# STM32F407_2.net
KiCad netlist of a schematic drawn in Altium Designer
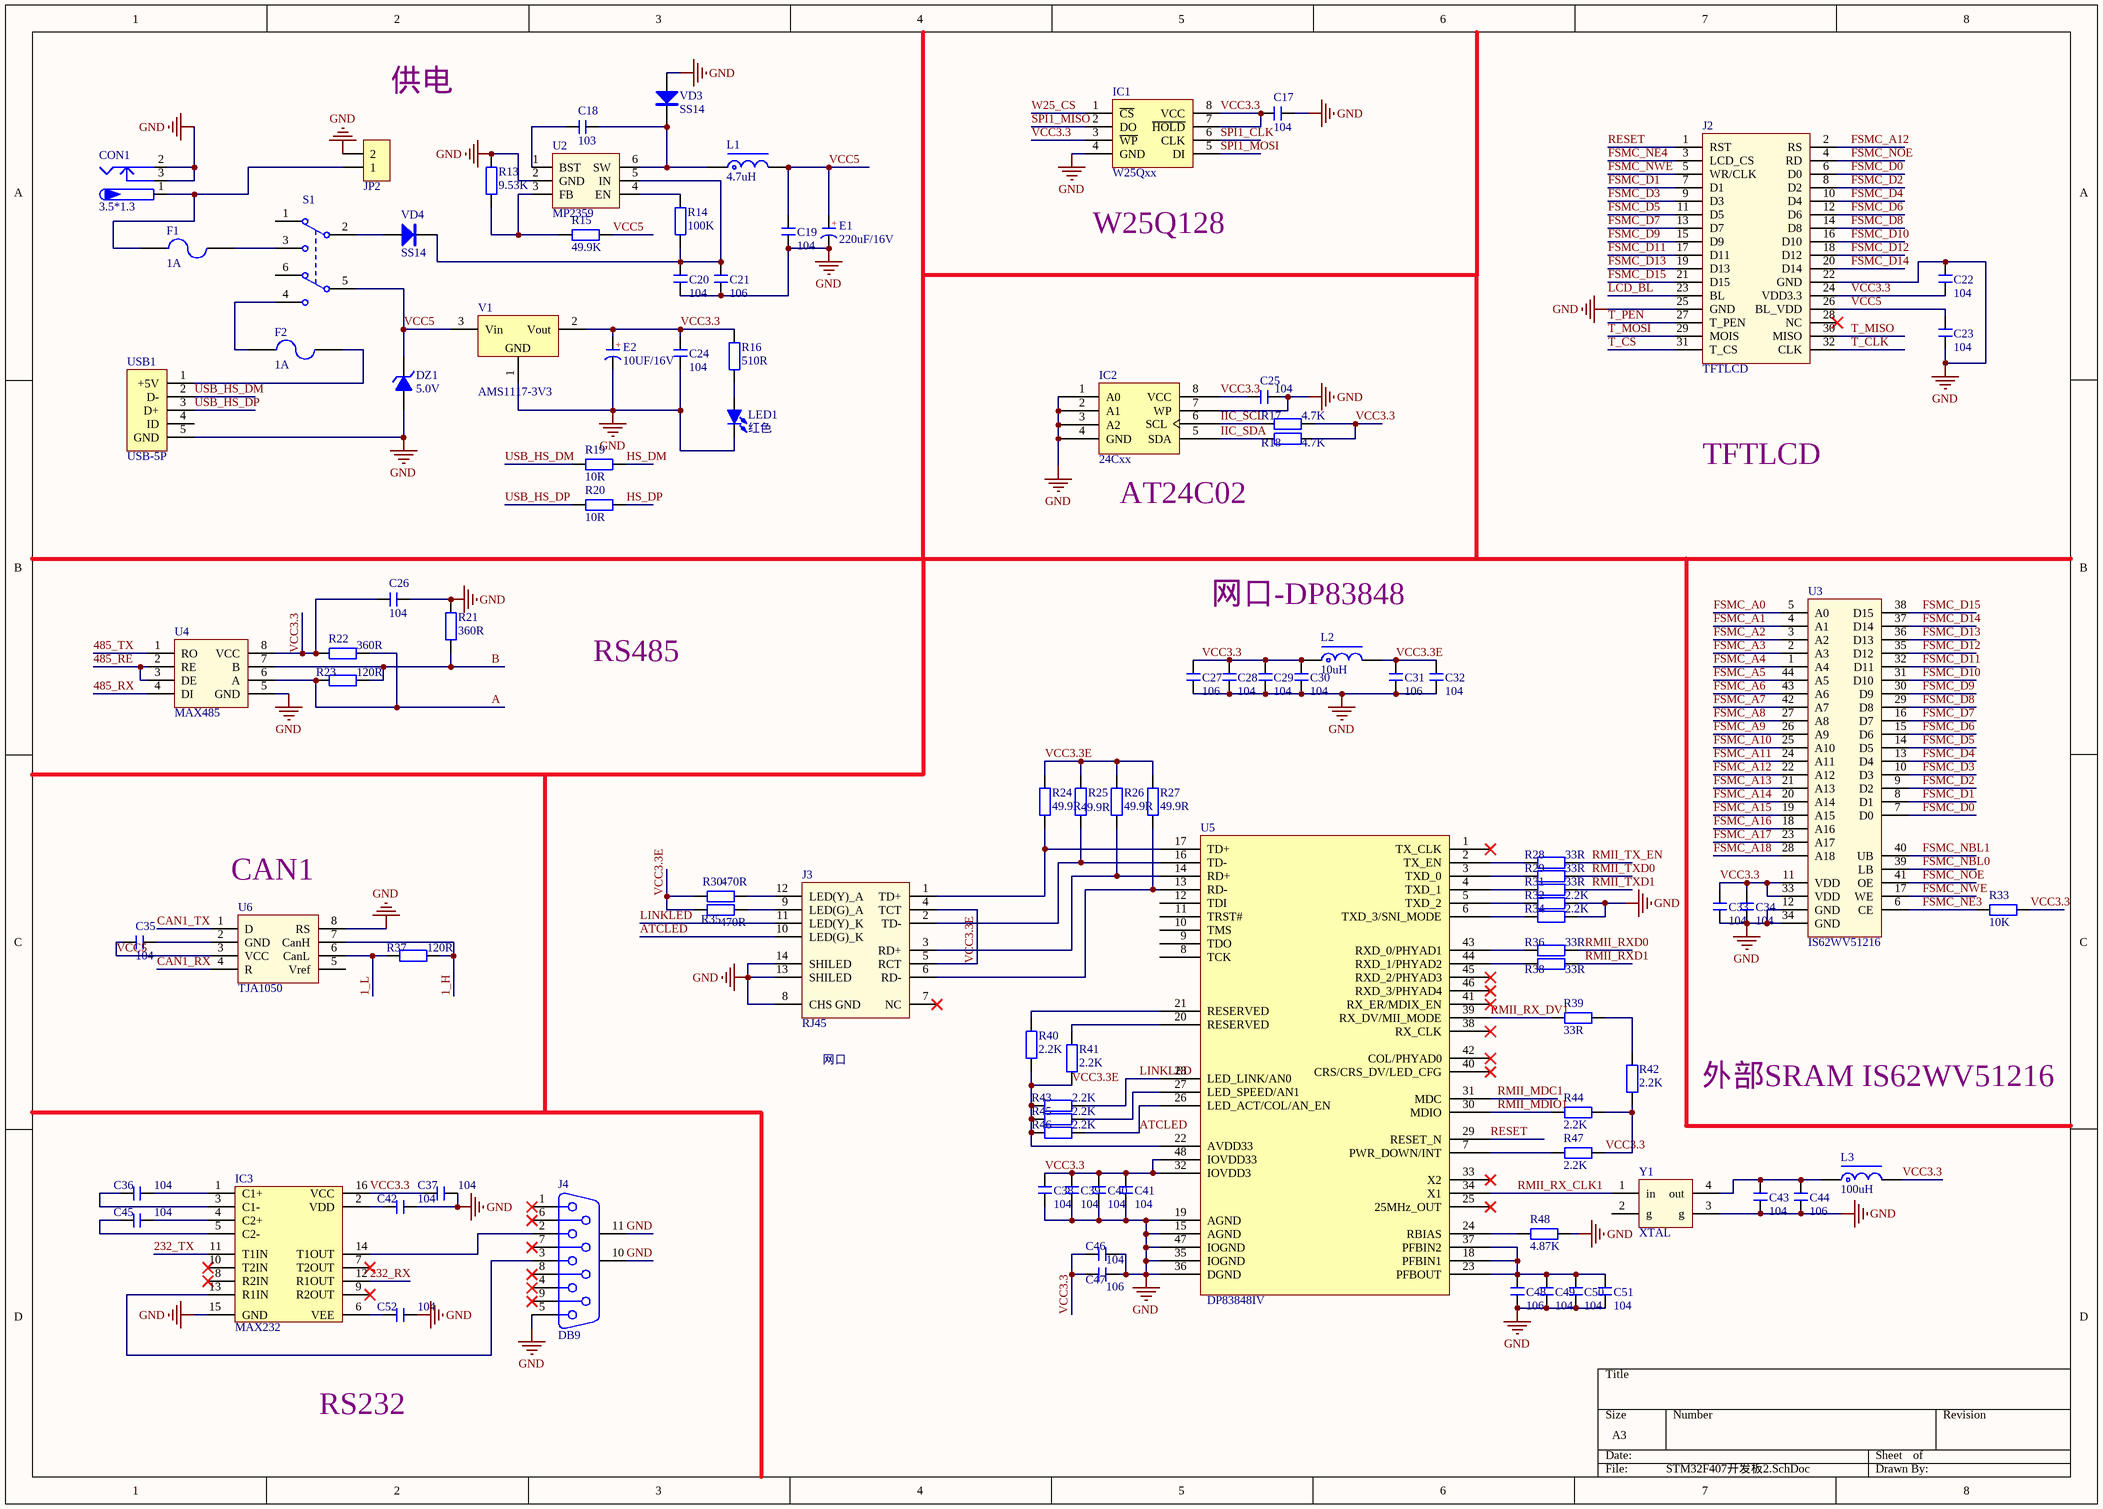
[diagram p0: STM32F407开发板2.SchDoc]

(export (version "E")
  (design (tool "Eeschema 10.0.6"))
  (components
    (comp (ref "C17")
      (value "104")
      (footprint "C 0603")
      (description "无极性贴片电容")
      (libsource (lib "电阻-电容-电感") (part "C"))
    )
    (comp (ref "C18")
      (value "103")
      (footprint "C 0603")
      (description "无极性贴片电容")
      (libsource (lib "电阻-电容-电感") (part "C"))
    )
    (comp (ref "C19")
      (value "104")
      (footprint "C 0603")
      (description "无极性贴片电容")
      (libsource (lib "电阻-电容-电感") (part "C"))
    )
    (comp (ref "C20")
      (value "104")
      (footprint "C 0603")
      (description "无极性贴片电容")
      (libsource (lib "电阻-电容-电感") (part "C"))
    )
    (comp (ref "C21")
      (value "106")
      (footprint "C 0603")
      (description "无极性贴片电容")
      (libsource (lib "电阻-电容-电感") (part "C"))
    )
    (comp (ref "C22")
      (value "104")
      (footprint "C 0603")
      (description "无极性贴片电容")
      (libsource (lib "电阻-电容-电感") (part "C"))
    )
    (comp (ref "C23")
      (value "104")
      (footprint "C 0603")
      (description "无极性贴片电容")
      (libsource (lib "电阻-电容-电感") (part "C"))
    )
    (comp (ref "C24")
      (value "104")
      (footprint "C 0603")
      (description "无极性贴片电容")
      (libsource (lib "电阻-电容-电感") (part "C"))
    )
    (comp (ref "C25")
      (value "104")
      (footprint "C 0603")
      (description "无极性贴片电容")
      (libsource (lib "电阻-电容-电感") (part "C"))
    )
    (comp (ref "C26")
      (value "104")
      (footprint "C 0603")
      (description "无极性贴片电容")
      (libsource (lib "电阻-电容-电感") (part "C"))
    )
    (comp (ref "C27")
      (value "106")
      (footprint "C 0603")
      (description "无极性贴片电容")
      (libsource (lib "电阻-电容-电感") (part "C"))
    )
    (comp (ref "C28")
      (value "104")
      (footprint "C 0603")
      (description "无极性贴片电容")
      (libsource (lib "电阻-电容-电感") (part "C"))
    )
    (comp (ref "C29")
      (value "104")
      (footprint "C 0603")
      (description "无极性贴片电容")
      (libsource (lib "电阻-电容-电感") (part "C"))
    )
    (comp (ref "C30")
      (value "104")
      (footprint "C 0603")
      (description "无极性贴片电容")
      (libsource (lib "电阻-电容-电感") (part "C"))
    )
    (comp (ref "C31")
      (value "106")
      (footprint "C 0603")
      (description "无极性贴片电容")
      (libsource (lib "电阻-电容-电感") (part "C"))
    )
    (comp (ref "C32")
      (value "104")
      (footprint "C 0603")
      (description "无极性贴片电容")
      (libsource (lib "电阻-电容-电感") (part "C"))
    )
    (comp (ref "C33")
      (value "104")
      (footprint "C 0603")
      (description "无极性贴片电容")
      (libsource (lib "电阻-电容-电感") (part "C"))
    )
    (comp (ref "C34")
      (value "104")
      (footprint "C 0603")
      (description "无极性贴片电容")
      (libsource (lib "电阻-电容-电感") (part "C"))
    )
    (comp (ref "C35")
      (value "104")
      (footprint "C 0603")
      (description "无极性贴片电容")
      (libsource (lib "电阻-电容-电感") (part "C"))
    )
    (comp (ref "C36")
      (value "104")
      (footprint "C 0603")
      (description "无极性贴片电容")
      (libsource (lib "电阻-电容-电感") (part "C"))
    )
    (comp (ref "C37")
      (value "104")
      (footprint "C 0603")
      (description "无极性贴片电容")
      (libsource (lib "电阻-电容-电感") (part "C"))
    )
    (comp (ref "C38")
      (value "104")
      (footprint "C 0603")
      (description "无极性贴片电容")
      (libsource (lib "电阻-电容-电感") (part "C"))
    )
    (comp (ref "C39")
      (value "104")
      (footprint "C 0603")
      (description "无极性贴片电容")
      (libsource (lib "电阻-电容-电感") (part "C"))
    )
    (comp (ref "C40")
      (value "104")
      (footprint "C 0603")
      (description "无极性贴片电容")
      (libsource (lib "电阻-电容-电感") (part "C"))
    )
    (comp (ref "C41")
      (value "104")
      (footprint "C 0603")
      (description "无极性贴片电容")
      (libsource (lib "电阻-电容-电感") (part "C"))
    )
    (comp (ref "C42")
      (value "104")
      (footprint "C 0603")
      (description "无极性贴片电容")
      (libsource (lib "电阻-电容-电感") (part "C"))
    )
    (comp (ref "C43")
      (value "104")
      (footprint "C 0603")
      (description "无极性贴片电容")
      (libsource (lib "电阻-电容-电感") (part "C"))
    )
    (comp (ref "C44")
      (value "106")
      (footprint "C 0603")
      (description "无极性贴片电容")
      (libsource (lib "电阻-电容-电感") (part "C"))
    )
    (comp (ref "C45")
      (value "104")
      (footprint "C 0603")
      (description "无极性贴片电容")
      (libsource (lib "电阻-电容-电感") (part "C"))
    )
    (comp (ref "C46")
      (value "104")
      (footprint "C 0603")
      (description "无极性贴片电容")
      (libsource (lib "电阻-电容-电感") (part "C"))
    )
    (comp (ref "C47")
      (value "106")
      (footprint "C 0603")
      (description "无极性贴片电容")
      (libsource (lib "电阻-电容-电感") (part "C"))
    )
    (comp (ref "C48")
      (value "106")
      (footprint "C 0603")
      (description "无极性贴片电容")
      (libsource (lib "电阻-电容-电感") (part "C"))
    )
    (comp (ref "C49")
      (value "104")
      (footprint "C 0603")
      (description "无极性贴片电容")
      (libsource (lib "电阻-电容-电感") (part "C"))
    )
    (comp (ref "C50")
      (value "104")
      (footprint "C 0603")
      (description "无极性贴片电容")
      (libsource (lib "电阻-电容-电感") (part "C"))
    )
    (comp (ref "C51")
      (value "104")
      (footprint "C 0603")
      (description "无极性贴片电容")
      (libsource (lib "电阻-电容-电感") (part "C"))
    )
    (comp (ref "C52")
      (value "104")
      (footprint "C 0603")
      (description "无极性贴片电容")
      (libsource (lib "电阻-电容-电感") (part "C"))
    )
    (comp (ref "CON1")
      (value "3.5*1.3")
      (footprint "DC_5.5MM")
      (description "低压电源接口")
      (libsource (lib "接口类") (part "P-DC"))
    )
    (comp (ref "DZ1")
      (value "5.0V")
      (footprint "MINI_MELF (LL34)")
      (description "12V/0.5W稳压管")
      (libsource (lib "二极管-整流桥") (part "1N4106"))
    )
    (comp (ref "E1")
      (value "220uF/16V")
      (footprint "CM D(6.3*7.7)")
      (description "直插电解电容")
      (libsource (lib "电阻-电容-电感") (part "C-CAP"))
    )
    (comp (ref "E2")
      (value "10UF/16V")
      (footprint "C 1206")
      (description "直插电解电容")
      (libsource (lib "电阻-电容-电感") (part "C-CAP"))
    )
    (comp (ref "F1")
      (value "1A")
      (footprint "L 1206")
      (description "5*20保险丝")
      (libsource (lib "保险丝-晶振") (part "FU 5x20"))
    )
    (comp (ref "F2")
      (value "1A")
      (footprint "L 1206")
      (description "5*20保险丝")
      (libsource (lib "保险丝-晶振") (part "FU 5x20"))
    )
    (comp (ref "IC1")
      (value "W25Qxx")
      (footprint "SOP8W_L")
      (description "外置Flash")
      (libsource (lib "IC芯片") (part "W25Qxx"))
    )
    (comp (ref "IC2")
      (value "24Cxx")
      (footprint "SOP8_L")
      (description "外置EEPROM")
      (libsource (lib "IC芯片") (part "24Cxx"))
    )
    (comp (ref "IC3") (value "MAX232") (footprint "SOP16_L") (libsource (lib "IC芯片") (part "MAX232")))
    (comp (ref "J2") (value "TFTLCD") (footprint "HDR-16X2") (libsource (lib "显示器件") (part "TFTLCD")))
    (comp (ref "J3") (value "RJ45") (footprint "HR911105A") (libsource (lib "IC芯片") (part "RJ45")))
    (comp (ref "J4")
      (value "DB9")
      (footprint "DB9/P_A")
      (description "9针串口")
      (libsource (lib "接口类") (part "DB9"))
    )
    (comp (ref "JP2")
      (value "HDR-1X2")
      (footprint "KF301-2P")
      (description "2P接插件")
      (libsource (lib "接插件") (part "Header 2"))
    )
    (comp (ref "L1")
      (value "4.7uH")
      (footprint "L 0603")
      (description "小功率贴片电感")
      (libsource (lib "电阻-电容-电感") (part "L"))
    )
    (comp (ref "L2")
      (value "10uH")
      (footprint "L 0603")
      (description "小功率贴片电感")
      (libsource (lib "电阻-电容-电感") (part "L"))
    )
    (comp (ref "L3")
      (value "100uH")
      (footprint "L 0603")
      (description "小功率贴片电感")
      (libsource (lib "电阻-电容-电感") (part "L"))
    )
    (comp (ref "LED1")
      (value "红色")
      (footprint "LED 0603R")
      (description "5mm插件LED")
      (libsource (lib "LED") (part "LED-5MM"))
    )
    (comp (ref "R13")
      (value "9.53K")
      (footprint "R 0603")
      (description "贴片电阻")
      (libsource (lib "电阻-电容-电感") (part "R"))
    )
    (comp (ref "R14")
      (value "100K")
      (footprint "R 0603")
      (description "贴片电阻")
      (libsource (lib "电阻-电容-电感") (part "R"))
    )
    (comp (ref "R15")
      (value "49.9K")
      (footprint "R 0603")
      (description "贴片电阻")
      (libsource (lib "电阻-电容-电感") (part "R"))
    )
    (comp (ref "R16")
      (value "510R")
      (footprint "R 0603")
      (description "贴片电阻")
      (libsource (lib "电阻-电容-电感") (part "R"))
    )
    (comp (ref "R17")
      (value "4.7K")
      (footprint "R 0603")
      (description "贴片电阻")
      (libsource (lib "电阻-电容-电感") (part "R"))
    )
    (comp (ref "R18")
      (value "4.7K")
      (footprint "R 0603")
      (description "贴片电阻")
      (libsource (lib "电阻-电容-电感") (part "R"))
    )
    (comp (ref "R19")
      (value "10R")
      (footprint "R 0603")
      (description "贴片电阻")
      (libsource (lib "电阻-电容-电感") (part "R"))
    )
    (comp (ref "R20")
      (value "10R")
      (footprint "R 0603")
      (description "贴片电阻")
      (libsource (lib "电阻-电容-电感") (part "R"))
    )
    (comp (ref "R21")
      (value "360R")
      (footprint "R 0603")
      (description "贴片电阻")
      (libsource (lib "电阻-电容-电感") (part "R"))
    )
    (comp (ref "R22")
      (value "360R")
      (footprint "R 0603")
      (description "贴片电阻")
      (libsource (lib "电阻-电容-电感") (part "R"))
    )
    (comp (ref "R23")
      (value "120R")
      (footprint "R 0603")
      (description "贴片电阻")
      (libsource (lib "电阻-电容-电感") (part "R"))
    )
    (comp (ref "R24")
      (value "49.9R")
      (footprint "R 0603")
      (description "贴片电阻")
      (libsource (lib "电阻-电容-电感") (part "R"))
    )
    (comp (ref "R25")
      (value "49.9R")
      (footprint "R 0603")
      (description "贴片电阻")
      (libsource (lib "电阻-电容-电感") (part "R"))
    )
    (comp (ref "R26")
      (value "49.9R")
      (footprint "R 0603")
      (description "贴片电阻")
      (libsource (lib "电阻-电容-电感") (part "R"))
    )
    (comp (ref "R27")
      (value "49.9R")
      (footprint "R 0603")
      (description "贴片电阻")
      (libsource (lib "电阻-电容-电感") (part "R"))
    )
    (comp (ref "R28")
      (value "33R")
      (footprint "R 0603")
      (description "贴片电阻")
      (libsource (lib "电阻-电容-电感") (part "R"))
    )
    (comp (ref "R29")
      (value "33R")
      (footprint "R 0603")
      (description "贴片电阻")
      (libsource (lib "电阻-电容-电感") (part "R"))
    )
    (comp (ref "R30")
      (value "470R")
      (footprint "R 0603")
      (description "贴片电阻")
      (libsource (lib "电阻-电容-电感") (part "R"))
    )
    (comp (ref "R31")
      (value "33R")
      (footprint "R 0603")
      (description "贴片电阻")
      (libsource (lib "电阻-电容-电感") (part "R"))
    )
    (comp (ref "R32")
      (value "2.2K")
      (footprint "R 0603")
      (description "贴片电阻")
      (libsource (lib "电阻-电容-电感") (part "R"))
    )
    (comp (ref "R33")
      (value "10K")
      (footprint "R 0603")
      (description "贴片电阻")
      (libsource (lib "电阻-电容-电感") (part "R"))
    )
    (comp (ref "R34")
      (value "2.2K")
      (footprint "R 0603")
      (description "贴片电阻")
      (libsource (lib "电阻-电容-电感") (part "R"))
    )
    (comp (ref "R35")
      (value "470R")
      (footprint "R 0603")
      (description "贴片电阻")
      (libsource (lib "电阻-电容-电感") (part "R"))
    )
    (comp (ref "R36")
      (value "33R")
      (footprint "R 0603")
      (description "贴片电阻")
      (libsource (lib "电阻-电容-电感") (part "R"))
    )
    (comp (ref "R37")
      (value "120R")
      (footprint "R 0603")
      (description "贴片电阻")
      (libsource (lib "电阻-电容-电感") (part "R"))
    )
    (comp (ref "R38")
      (value "33R")
      (footprint "R 0603")
      (description "贴片电阻")
      (libsource (lib "电阻-电容-电感") (part "R"))
    )
    (comp (ref "R39")
      (value "33R")
      (footprint "R 0603")
      (description "贴片电阻")
      (libsource (lib "电阻-电容-电感") (part "R"))
    )
    (comp (ref "R40")
      (value "2.2K")
      (footprint "R 0603")
      (description "贴片电阻")
      (libsource (lib "电阻-电容-电感") (part "R"))
    )
    (comp (ref "R41")
      (value "2.2K")
      (footprint "R 0603")
      (description "贴片电阻")
      (libsource (lib "电阻-电容-电感") (part "R"))
    )
    (comp (ref "R42")
      (value "2.2K")
      (footprint "R 0603")
      (description "贴片电阻")
      (libsource (lib "电阻-电容-电感") (part "R"))
    )
    (comp (ref "R43")
      (value "2.2K")
      (footprint "R 0603")
      (description "贴片电阻")
      (libsource (lib "电阻-电容-电感") (part "R"))
    )
    (comp (ref "R44")
      (value "2.2K")
      (footprint "R 0603")
      (description "贴片电阻")
      (libsource (lib "电阻-电容-电感") (part "R"))
    )
    (comp (ref "R45")
      (value "2.2K")
      (footprint "R 0603")
      (description "贴片电阻")
      (libsource (lib "电阻-电容-电感") (part "R"))
    )
    (comp (ref "R46")
      (value "2.2K")
      (footprint "R 0603")
      (description "贴片电阻")
      (libsource (lib "电阻-电容-电感") (part "R"))
    )
    (comp (ref "R47")
      (value "2.2K")
      (footprint "R 0603")
      (description "贴片电阻")
      (libsource (lib "电阻-电容-电感") (part "R"))
    )
    (comp (ref "R48")
      (value "4.87K")
      (footprint "R 0603")
      (description "贴片电阻")
      (libsource (lib "电阻-电容-电感") (part "R"))
    )
    (comp (ref "S1")
      (value "SK-22D02")
      (footprint "KFT DIP-8X8")
      (description "2路波动开关")
      (libsource (lib "按键-开关") (part "SSW-2P"))
    )
    (comp (ref "U2") (value "MP2359") (footprint "MP2359") (libsource (lib "IC芯片") (part "MP2359")))
    (comp (ref "U3")
      (value "IS62WV51216")
      (footprint "IS62WV51216")
      (libsource (lib "IC芯片") (part "IS62WV51216"))
    )
    (comp (ref "U4") (value "MAX485") (footprint "MAX485") (libsource (lib "IC芯片") (part "MAX485")))
    (comp (ref "U5")
      (value "DP83848IV")
      (footprint "LQFP48 7X7_L")
      (libsource (lib "IC芯片") (part "DP83848IV"))
    )
    (comp (ref "U6") (value "TJA1050") (footprint "TJA1050") (libsource (lib "IC芯片") (part "TJA1050")))
    (comp (ref "USB1")
      (value "USB-5P")
      (footprint "USB-MINI-A")
      (description "微型USB母座")
      (libsource (lib "接口类") (part "USB-5P"))
    )
    (comp (ref "V1")
      (value "AMS1117-3V3")
      (footprint "SOT223_L")
      (description "三端稳压芯片")
      (libsource (lib "IC芯片") (part "AMS1117"))
    )
    (comp (ref "VD3")
      (value "SS14")
      (footprint "SOD-123")
      (description "肖特基二极管")
      (libsource (lib "二极管-整流桥") (part "SS14"))
    )
    (comp (ref "VD4")
      (value "SS14")
      (footprint "SOD-123")
      (description "肖特基二极管")
      (libsource (lib "二极管-整流桥") (part "SS14"))
    )
    (comp (ref "Y1") (value "XTAL") (footprint "XTAL-5032") (libsource (lib "保险丝-晶振") (part "XTAL")))
  )
  (nets
    (net (code "1") (name "/1_H") (class "Default")
      (node (ref "R37") (pin "1") (pinfunction "1_1") (pintype "passive"))
      (node (ref "U6") (pin "7") (pinfunction "CanH_7") (pintype "passive"))
    )
    (net (code "2") (name "/1_L") (class "Default")
      (node (ref "R37") (pin "2") (pinfunction "2_2") (pintype "passive"))
      (node (ref "U6") (pin "6") (pinfunction "CanL_6") (pintype "passive"))
    )
    (net (code "3") (name "/232_RX") (class "Default")
      (node (ref "IC3") (pin "12") (pinfunction "R1OUT_12") (pintype "passive"))
    )
    (net (code "4") (name "/232_TX") (class "Default")
      (node (ref "IC3") (pin "11") (pinfunction "T1IN_11") (pintype "passive"))
    )
    (net (code "5") (name "/485_RE") (class "Default")
      (node (ref "U4") (pin "2") (pinfunction "RE_2") (pintype "passive"))
      (node (ref "U4") (pin "3") (pinfunction "DE_3") (pintype "passive"))
    )
    (net (code "6") (name "/485_RX") (class "Default")
      (node (ref "U4") (pin "4") (pinfunction "DI_4") (pintype "passive"))
    )
    (net (code "7") (name "/485_TX") (class "Default")
      (node (ref "U4") (pin "1") (pinfunction "RO_1") (pintype "passive"))
    )
    (net (code "8") (name "/A") (class "Default")
      (node (ref "R22") (pin "1") (pinfunction "1_1") (pintype "passive"))
      (node (ref "R23") (pin "2") (pinfunction "2_2") (pintype "passive"))
      (node (ref "U4") (pin "6") (pinfunction "A_6") (pintype "passive"))
    )
    (net (code "9") (name "/ATCLED") (class "Default")
      (node (ref "J3") (pin "10") (pinfunction "LED(G)_K_10") (pintype "passive"))
      (node (ref "R46") (pin "1") (pinfunction "1_1") (pintype "passive"))
      (node (ref "U5") (pin "26") (pinfunction "LED_ACT/COL/AN_EN_26") (pintype "passive"))
    )
    (net (code "10") (name "/B") (class "Default")
      (node (ref "R21") (pin "2") (pinfunction "2_2") (pintype "passive"))
      (node (ref "R23") (pin "1") (pinfunction "1_1") (pintype "passive"))
      (node (ref "U4") (pin "7") (pinfunction "B_7") (pintype "passive"))
    )
    (net (code "11") (name "/CAN1_RX") (class "Default")
      (node (ref "U6") (pin "4") (pinfunction "R_4") (pintype "passive"))
    )
    (net (code "12") (name "/CAN1_TX") (class "Default")
      (node (ref "U6") (pin "1") (pinfunction "D_1") (pintype "passive"))
    )
    (net (code "13") (name "/FSMC_A0") (class "Default")
      (node (ref "U3") (pin "5") (pinfunction "A0_5") (pintype "passive"))
    )
    (net (code "14") (name "/FSMC_A1") (class "Default")
      (node (ref "U3") (pin "4") (pinfunction "A1_4") (pintype "passive"))
    )
    (net (code "15") (name "/FSMC_A2") (class "Default")
      (node (ref "U3") (pin "3") (pinfunction "A2_3") (pintype "passive"))
    )
    (net (code "16") (name "/FSMC_A3") (class "Default")
      (node (ref "U3") (pin "2") (pinfunction "A3_2") (pintype "passive"))
    )
    (net (code "17") (name "/FSMC_A4") (class "Default")
      (node (ref "U3") (pin "1") (pinfunction "A4_1") (pintype "passive"))
    )
    (net (code "18") (name "/FSMC_A5") (class "Default")
      (node (ref "U3") (pin "44") (pinfunction "A5_44") (pintype "passive"))
    )
    (net (code "19") (name "/FSMC_A6") (class "Default")
      (node (ref "U3") (pin "43") (pinfunction "A6_43") (pintype "passive"))
    )
    (net (code "20") (name "/FSMC_A7") (class "Default")
      (node (ref "U3") (pin "42") (pinfunction "A7_42") (pintype "passive"))
    )
    (net (code "21") (name "/FSMC_A8") (class "Default")
      (node (ref "U3") (pin "27") (pinfunction "A8_27") (pintype "passive"))
    )
    (net (code "22") (name "/FSMC_A9") (class "Default")
      (node (ref "U3") (pin "26") (pinfunction "A9_26") (pintype "passive"))
    )
    (net (code "23") (name "/FSMC_A10") (class "Default")
      (node (ref "U3") (pin "25") (pinfunction "A10_25") (pintype "passive"))
    )
    (net (code "24") (name "/FSMC_A11") (class "Default")
      (node (ref "U3") (pin "24") (pinfunction "A11_24") (pintype "passive"))
    )
    (net (code "25") (name "/FSMC_A12") (class "Default")
      (node (ref "J2") (pin "2") (pinfunction "RS_2") (pintype "passive"))
      (node (ref "U3") (pin "22") (pinfunction "A12_22") (pintype "passive"))
    )
    (net (code "26") (name "/FSMC_A13") (class "Default")
      (node (ref "U3") (pin "21") (pinfunction "A13_21") (pintype "passive"))
    )
    (net (code "27") (name "/FSMC_A14") (class "Default")
      (node (ref "U3") (pin "20") (pinfunction "A14_20") (pintype "passive"))
    )
    (net (code "28") (name "/FSMC_A15") (class "Default")
      (node (ref "U3") (pin "19") (pinfunction "A15_19") (pintype "passive"))
    )
    (net (code "29") (name "/FSMC_A16") (class "Default")
      (node (ref "U3") (pin "18") (pinfunction "A16_18") (pintype "passive"))
    )
    (net (code "30") (name "/FSMC_A17") (class "Default")
      (node (ref "U3") (pin "23") (pinfunction "A17_23") (pintype "passive"))
    )
    (net (code "31") (name "/FSMC_A18") (class "Default")
      (node (ref "U3") (pin "28") (pinfunction "A18_28") (pintype "passive"))
    )
    (net (code "32") (name "/FSMC_D0") (class "Default")
      (node (ref "J2") (pin "6") (pinfunction "D0_6") (pintype "passive"))
      (node (ref "U3") (pin "7") (pinfunction "D0_7") (pintype "passive"))
    )
    (net (code "33") (name "/FSMC_D1") (class "Default")
      (node (ref "J2") (pin "7") (pinfunction "D1_7") (pintype "passive"))
      (node (ref "U3") (pin "8") (pinfunction "D1_8") (pintype "passive"))
    )
    (net (code "34") (name "/FSMC_D2") (class "Default")
      (node (ref "J2") (pin "8") (pinfunction "D2_8") (pintype "passive"))
      (node (ref "U3") (pin "9") (pinfunction "D2_9") (pintype "passive"))
    )
    (net (code "35") (name "/FSMC_D3") (class "Default")
      (node (ref "J2") (pin "9") (pinfunction "D3_9") (pintype "passive"))
      (node (ref "U3") (pin "10") (pinfunction "D3_10") (pintype "passive"))
    )
    (net (code "36") (name "/FSMC_D4") (class "Default")
      (node (ref "J2") (pin "10") (pinfunction "D4_10") (pintype "passive"))
      (node (ref "U3") (pin "13") (pinfunction "D4_13") (pintype "passive"))
    )
    (net (code "37") (name "/FSMC_D5") (class "Default")
      (node (ref "J2") (pin "11") (pinfunction "D5_11") (pintype "passive"))
      (node (ref "U3") (pin "14") (pinfunction "D5_14") (pintype "passive"))
    )
    (net (code "38") (name "/FSMC_D6") (class "Default")
      (node (ref "J2") (pin "12") (pinfunction "D6_12") (pintype "passive"))
      (node (ref "U3") (pin "15") (pinfunction "D6_15") (pintype "passive"))
    )
    (net (code "39") (name "/FSMC_D7") (class "Default")
      (node (ref "J2") (pin "13") (pinfunction "D7_13") (pintype "passive"))
      (node (ref "U3") (pin "16") (pinfunction "D7_16") (pintype "passive"))
    )
    (net (code "40") (name "/FSMC_D8") (class "Default")
      (node (ref "J2") (pin "14") (pinfunction "D8_14") (pintype "passive"))
      (node (ref "U3") (pin "29") (pinfunction "D8_29") (pintype "passive"))
    )
    (net (code "41") (name "/FSMC_D9") (class "Default")
      (node (ref "J2") (pin "15") (pinfunction "D9_15") (pintype "passive"))
      (node (ref "U3") (pin "30") (pinfunction "D9_30") (pintype "passive"))
    )
    (net (code "42") (name "/FSMC_D10") (class "Default")
      (node (ref "J2") (pin "16") (pinfunction "D10_16") (pintype "passive"))
      (node (ref "U3") (pin "31") (pinfunction "D10_31") (pintype "passive"))
    )
    (net (code "43") (name "/FSMC_D11") (class "Default")
      (node (ref "J2") (pin "17") (pinfunction "D11_17") (pintype "passive"))
      (node (ref "U3") (pin "32") (pinfunction "D11_32") (pintype "passive"))
    )
    (net (code "44") (name "/FSMC_D12") (class "Default")
      (node (ref "J2") (pin "18") (pinfunction "D12_18") (pintype "passive"))
      (node (ref "U3") (pin "35") (pinfunction "D12_35") (pintype "passive"))
    )
    (net (code "45") (name "/FSMC_D13") (class "Default")
      (node (ref "J2") (pin "19") (pinfunction "D13_19") (pintype "passive"))
      (node (ref "U3") (pin "36") (pinfunction "D13_36") (pintype "passive"))
    )
    (net (code "46") (name "/FSMC_D14") (class "Default")
      (node (ref "J2") (pin "20") (pinfunction "D14_20") (pintype "passive"))
      (node (ref "U3") (pin "37") (pinfunction "D14_37") (pintype "passive"))
    )
    (net (code "47") (name "/FSMC_D15") (class "Default")
      (node (ref "J2") (pin "21") (pinfunction "D15_21") (pintype "passive"))
      (node (ref "U3") (pin "38") (pinfunction "D15_38") (pintype "passive"))
    )
    (net (code "48") (name "/FSMC_NBL0") (class "Default")
      (node (ref "U3") (pin "39") (pinfunction "LB_39") (pintype "passive"))
    )
    (net (code "49") (name "/FSMC_NBL1") (class "Default")
      (node (ref "U3") (pin "40") (pinfunction "UB_40") (pintype "passive"))
    )
    (net (code "50") (name "/FSMC_NE3") (class "Default")
      (node (ref "R33") (pin "2") (pinfunction "2_2") (pintype "passive"))
      (node (ref "U3") (pin "6") (pinfunction "CE_6") (pintype "passive"))
    )
    (net (code "51") (name "/FSMC_NE4") (class "Default")
      (node (ref "J2") (pin "3") (pinfunction "LCD_CS_3") (pintype "passive"))
    )
    (net (code "52") (name "/FSMC_NOE") (class "Default")
      (node (ref "J2") (pin "4") (pinfunction "RD_4") (pintype "passive"))
      (node (ref "U3") (pin "41") (pinfunction "OE_41") (pintype "passive"))
    )
    (net (code "53") (name "/FSMC_NWE") (class "Default")
      (node (ref "J2") (pin "5") (pinfunction "WR/CLK_5") (pintype "passive"))
      (node (ref "U3") (pin "17") (pinfunction "WE_17") (pintype "passive"))
    )
    (net (code "54") (name "/HS_DM") (class "Default")
      (node (ref "R19") (pin "1") (pinfunction "1_1") (pintype "passive"))
    )
    (net (code "55") (name "/HS_DP") (class "Default")
      (node (ref "R20") (pin "1") (pinfunction "1_1") (pintype "passive"))
    )
    (net (code "56") (name "/IIC_SCL") (class "Default")
      (node (ref "IC2") (pin "6") (pinfunction "SCL_6") (pintype "passive"))
      (node (ref "R17") (pin "2") (pinfunction "2_2") (pintype "passive"))
    )
    (net (code "57") (name "/IIC_SDA") (class "Default")
      (node (ref "IC2") (pin "5") (pinfunction "SDA_5") (pintype "passive"))
      (node (ref "R18") (pin "2") (pinfunction "2_2") (pintype "passive"))
    )
    (net (code "58") (name "/LCD_BL") (class "Default")
      (node (ref "J2") (pin "23") (pinfunction "BL_23") (pintype "passive"))
    )
    (net (code "59") (name "/LINKLED") (class "Default")
      (node (ref "J3") (pin "11") (pinfunction "LED(Y)_K_11") (pintype "passive"))
      (node (ref "R43") (pin "1") (pinfunction "1_1") (pintype "passive"))
      (node (ref "U5") (pin "28") (pinfunction "LED_LINK/AN0_28") (pintype "passive"))
    )
    (net (code "60") (name "/RESET") (class "Default")
      (node (ref "J2") (pin "1") (pinfunction "RST_1") (pintype "passive"))
      (node (ref "U5") (pin "29") (pinfunction "RESET_N_29") (pintype "passive"))
    )
    (net (code "61") (name "/RMII_MDC1") (class "Default")
      (node (ref "U5") (pin "31") (pinfunction "MDC_31") (pintype "passive"))
    )
    (net (code "62") (name "/RMII_MDIO1") (class "Default")
      (node (ref "R44") (pin "1") (pinfunction "1_1") (pintype "passive"))
      (node (ref "U5") (pin "30") (pinfunction "MDIO_30") (pintype "passive"))
    )
    (net (code "63") (name "/RMII_RXD0") (class "Default")
      (node (ref "R36") (pin "2") (pinfunction "2_2") (pintype "passive"))
    )
    (net (code "64") (name "/RMII_RXD1") (class "Default")
      (node (ref "R38") (pin "2") (pinfunction "2_2") (pintype "passive"))
    )
    (net (code "65") (name "/RMII_RX_CLK1") (class "Default")
      (node (ref "U5") (pin "34") (pinfunction "X1_34") (pintype "passive"))
      (node (ref "Y1") (pin "1") (pinfunction "in_1") (pintype "passive"))
    )
    (net (code "66") (name "/RMII_RX_DV1") (class "Default")
      (node (ref "R39") (pin "1") (pinfunction "1_1") (pintype "passive"))
      (node (ref "U5") (pin "39") (pinfunction "RX_DV/MII_MODE_39") (pintype "passive"))
    )
    (net (code "67") (name "/RMII_TXD0") (class "Default")
      (node (ref "R29") (pin "2") (pinfunction "2_2") (pintype "passive"))
    )
    (net (code "68") (name "/RMII_TXD1") (class "Default")
      (node (ref "R31") (pin "2") (pinfunction "2_2") (pintype "passive"))
    )
    (net (code "69") (name "/RMII_TX_EN") (class "Default")
      (node (ref "R28") (pin "2") (pinfunction "2_2") (pintype "passive"))
    )
    (net (code "70") (name "/SPI1_CLK") (class "Default")
      (node (ref "IC1") (pin "6") (pinfunction "CLK_6") (pintype "passive"))
    )
    (net (code "71") (name "/SPI1_MISO") (class "Default")
      (node (ref "IC1") (pin "2") (pinfunction "DO_2") (pintype "passive"))
    )
    (net (code "72") (name "/SPI1_MOSI") (class "Default")
      (node (ref "IC1") (pin "5") (pinfunction "DI_5") (pintype "passive"))
    )
    (net (code "73") (name "/T_CLK") (class "Default")
      (node (ref "J2") (pin "32") (pinfunction "CLK_32") (pintype "passive"))
    )
    (net (code "74") (name "/T_CS") (class "Default")
      (node (ref "J2") (pin "31") (pinfunction "T_CS_31") (pintype "passive"))
    )
    (net (code "75") (name "/T_MISO") (class "Default")
      (node (ref "J2") (pin "30") (pinfunction "MISO_30") (pintype "passive"))
    )
    (net (code "76") (name "/T_MOSI") (class "Default")
      (node (ref "J2") (pin "29") (pinfunction "MOIS_29") (pintype "passive"))
    )
    (net (code "77") (name "/T_PEN") (class "Default")
      (node (ref "J2") (pin "27") (pinfunction "T_PEN_27") (pintype "passive"))
    )
    (net (code "78") (name "/USB_HS_DM") (class "Default")
      (node (ref "R19") (pin "2") (pinfunction "2_2") (pintype "passive"))
      (node (ref "USB1") (pin "2") (pinfunction "D-_2") (pintype "passive"))
    )
    (net (code "79") (name "/USB_HS_DP") (class "Default")
      (node (ref "R20") (pin "2") (pinfunction "2_2") (pintype "passive"))
      (node (ref "USB1") (pin "3") (pinfunction "D+_3") (pintype "passive"))
    )
    (net (code "80") (name "/VCC3.3") (class "Default")
      (node (ref "C17") (pin "2") (pinfunction "2_2") (pintype "passive"))
      (node (ref "C22") (pin "2") (pinfunction "2_2") (pintype "passive"))
      (node (ref "C24") (pin "2") (pinfunction "2_2") (pintype "passive"))
      (node (ref "C25") (pin "2") (pinfunction "2_2") (pintype "passive"))
      (node (ref "C26") (pin "2") (pinfunction "2_2") (pintype "passive"))
      (node (ref "C27") (pin "1") (pinfunction "1_1") (pintype "passive"))
      (node (ref "C28") (pin "1") (pinfunction "1_1") (pintype "passive"))
      (node (ref "C29") (pin "1") (pinfunction "1_1") (pintype "passive"))
      (node (ref "C30") (pin "1") (pinfunction "1_1") (pintype "passive"))
      (node (ref "C33") (pin "1") (pinfunction "1_1") (pintype "passive"))
      (node (ref "C34") (pin "1") (pinfunction "1_1") (pintype "passive"))
      (node (ref "C37") (pin "2") (pinfunction "2_2") (pintype "passive"))
      (node (ref "C38") (pin "1") (pinfunction "1_1") (pintype "passive"))
      (node (ref "C39") (pin "1") (pinfunction "1_1") (pintype "passive"))
      (node (ref "C40") (pin "1") (pinfunction "1_1") (pintype "passive"))
      (node (ref "C41") (pin "1") (pinfunction "1_1") (pintype "passive"))
      (node (ref "C46") (pin "1") (pinfunction "1_1") (pintype "passive"))
      (node (ref "C47") (pin "1") (pinfunction "1_1") (pintype "passive"))
      (node (ref "E2") (pin "1") (pinfunction "A_1") (pintype "passive"))
      (node (ref "IC1") (pin "3") (pinfunction "~{WP}_3") (pintype "passive"))
      (node (ref "IC1") (pin "7") (pinfunction "~{HOLD}_7") (pintype "passive"))
      (node (ref "IC1") (pin "8") (pinfunction "VCC_8") (pintype "passive"))
      (node (ref "IC2") (pin "8") (pinfunction "VCC_8") (pintype "power_in"))
      (node (ref "IC3") (pin "16") (pinfunction "VCC_16") (pintype "passive"))
      (node (ref "J2") (pin "24") (pinfunction "VDD3.3_24") (pintype "passive"))
      (node (ref "L2") (pin "1") (pinfunction "1_1") (pintype "passive"))
      (node (ref "L3") (pin "2") (pinfunction "2_2") (pintype "passive"))
      (node (ref "R16") (pin "2") (pinfunction "2_2") (pintype "passive"))
      (node (ref "R17") (pin "1") (pinfunction "1_1") (pintype "passive"))
      (node (ref "R18") (pin "1") (pinfunction "1_1") (pintype "passive"))
      (node (ref "R22") (pin "2") (pinfunction "2_2") (pintype "passive"))
      (node (ref "R33") (pin "1") (pinfunction "1_1") (pintype "passive"))
      (node (ref "R42") (pin "1") (pinfunction "1_1") (pintype "passive"))
      (node (ref "R44") (pin "2") (pinfunction "2_2") (pintype "passive"))
      (node (ref "R47") (pin "2") (pinfunction "2_2") (pintype "passive"))
      (node (ref "U3") (pin "11") (pinfunction "VDD_11") (pintype "passive"))
      (node (ref "U3") (pin "33") (pinfunction "VDD_33") (pintype "passive"))
      (node (ref "U4") (pin "8") (pinfunction "VCC_8") (pintype "passive"))
      (node (ref "U5") (pin "32") (pinfunction "IOVDD3_32") (pintype "passive"))
      (node (ref "U5") (pin "48") (pinfunction "IOVDD33_48") (pintype "passive"))
      (node (ref "V1") (pin "2") (pinfunction "Vout_2") (pintype "passive"))
    )
    (net (code "81") (name "/VCC3.3E") (class "Default")
      (node (ref "C31") (pin "1") (pinfunction "1_1") (pintype "passive"))
      (node (ref "C32") (pin "1") (pinfunction "1_1") (pintype "passive"))
      (node (ref "J3") (pin "4") (pinfunction "TCT_4") (pintype "passive"))
      (node (ref "J3") (pin "5") (pinfunction "RCT_5") (pintype "passive"))
      (node (ref "L2") (pin "2") (pinfunction "2_2") (pintype "passive"))
      (node (ref "R24") (pin "1") (pinfunction "1_1") (pintype "passive"))
      (node (ref "R25") (pin "1") (pinfunction "1_1") (pintype "passive"))
      (node (ref "R26") (pin "1") (pinfunction "1_1") (pintype "passive"))
      (node (ref "R27") (pin "1") (pinfunction "1_1") (pintype "passive"))
      (node (ref "R30") (pin "2") (pinfunction "2_2") (pintype "passive"))
      (node (ref "R35") (pin "2") (pinfunction "2_2") (pintype "passive"))
      (node (ref "R40") (pin "2") (pinfunction "2_2") (pintype "passive"))
      (node (ref "R41") (pin "2") (pinfunction "2_2") (pintype "passive"))
      (node (ref "R43") (pin "2") (pinfunction "2_2") (pintype "passive"))
      (node (ref "R45") (pin "2") (pinfunction "2_2") (pintype "passive"))
      (node (ref "R46") (pin "2") (pinfunction "2_2") (pintype "passive"))
      (node (ref "U5") (pin "22") (pinfunction "AVDD33_22") (pintype "passive"))
    )
    (net (code "82") (name "/VCC5") (class "Default")
      (node (ref "C19") (pin "2") (pinfunction "2_2") (pintype "passive"))
      (node (ref "C23") (pin "1") (pinfunction "1_1") (pintype "passive"))
      (node (ref "C35") (pin "2") (pinfunction "2_2") (pintype "passive"))
      (node (ref "DZ1") (pin "2") (pinfunction "K_2") (pintype "passive"))
      (node (ref "E1") (pin "1") (pinfunction "A_1") (pintype "passive"))
      (node (ref "J2") (pin "26") (pinfunction "BL_VDD_26") (pintype "passive"))
      (node (ref "L1") (pin "2") (pinfunction "2_2") (pintype "passive"))
      (node (ref "R15") (pin "1") (pinfunction "1_1") (pintype "passive"))
      (node (ref "S1") (pin "5") (pinfunction "5_5") (pintype "passive"))
      (node (ref "U6") (pin "3") (pinfunction "VCC_3") (pintype "passive"))
      (node (ref "V1") (pin "3") (pinfunction "Vin_3") (pintype "passive"))
    )
    (net (code "83") (name "/W25_CS") (class "Default")
      (node (ref "IC1") (pin "1") (pinfunction "~{CS}_1") (pintype "passive"))
    )
    (net (code "84") (name "GND") (class "Default")
      (node (ref "C17") (pin "1") (pinfunction "1_1") (pintype "passive"))
      (node (ref "C19") (pin "1") (pinfunction "1_1") (pintype "passive"))
      (node (ref "C20") (pin "1") (pinfunction "1_1") (pintype "passive"))
      (node (ref "C21") (pin "1") (pinfunction "1_1") (pintype "passive"))
      (node (ref "C22") (pin "1") (pinfunction "1_1") (pintype "passive"))
      (node (ref "C23") (pin "2") (pinfunction "2_2") (pintype "passive"))
      (node (ref "C24") (pin "1") (pinfunction "1_1") (pintype "passive"))
      (node (ref "C25") (pin "1") (pinfunction "1_1") (pintype "passive"))
      (node (ref "C26") (pin "1") (pinfunction "1_1") (pintype "passive"))
      (node (ref "C27") (pin "2") (pinfunction "2_2") (pintype "passive"))
      (node (ref "C28") (pin "2") (pinfunction "2_2") (pintype "passive"))
      (node (ref "C29") (pin "2") (pinfunction "2_2") (pintype "passive"))
      (node (ref "C30") (pin "2") (pinfunction "2_2") (pintype "passive"))
      (node (ref "C31") (pin "2") (pinfunction "2_2") (pintype "passive"))
      (node (ref "C32") (pin "2") (pinfunction "2_2") (pintype "passive"))
      (node (ref "C33") (pin "2") (pinfunction "2_2") (pintype "passive"))
      (node (ref "C34") (pin "2") (pinfunction "2_2") (pintype "passive"))
      (node (ref "C37") (pin "1") (pinfunction "1_1") (pintype "passive"))
      (node (ref "C38") (pin "2") (pinfunction "2_2") (pintype "passive"))
      (node (ref "C39") (pin "2") (pinfunction "2_2") (pintype "passive"))
      (node (ref "C40") (pin "2") (pinfunction "2_2") (pintype "passive"))
      (node (ref "C41") (pin "2") (pinfunction "2_2") (pintype "passive"))
      (node (ref "C42") (pin "1") (pinfunction "1_1") (pintype "passive"))
      (node (ref "C43") (pin "2") (pinfunction "2_2") (pintype "passive"))
      (node (ref "C44") (pin "2") (pinfunction "2_2") (pintype "passive"))
      (node (ref "C46") (pin "2") (pinfunction "2_2") (pintype "passive"))
      (node (ref "C47") (pin "2") (pinfunction "2_2") (pintype "passive"))
      (node (ref "C48") (pin "2") (pinfunction "2_2") (pintype "passive"))
      (node (ref "C49") (pin "2") (pinfunction "2_2") (pintype "passive"))
      (node (ref "C50") (pin "2") (pinfunction "2_2") (pintype "passive"))
      (node (ref "C51") (pin "2") (pinfunction "2_2") (pintype "passive"))
      (node (ref "C52") (pin "1") (pinfunction "1_1") (pintype "passive"))
      (node (ref "CON1") (pin "2") (pintype "power_in"))
      (node (ref "CON1") (pin "3") (pintype "power_in"))
      (node (ref "DZ1") (pin "1") (pinfunction "A_1") (pintype "passive"))
      (node (ref "E1") (pin "2") (pinfunction "K_2") (pintype "passive"))
      (node (ref "E2") (pin "2") (pinfunction "K_2") (pintype "passive"))
      (node (ref "IC1") (pin "4") (pinfunction "GND_4") (pintype "passive"))
      (node (ref "IC2") (pin "1") (pinfunction "A0_1") (pintype "passive"))
      (node (ref "IC2") (pin "2") (pinfunction "A1_2") (pintype "passive"))
      (node (ref "IC2") (pin "3") (pinfunction "A2_3") (pintype "passive"))
      (node (ref "IC2") (pin "4") (pinfunction "GND_4") (pintype "passive"))
      (node (ref "IC2") (pin "7") (pinfunction "WP_7") (pintype "passive"))
      (node (ref "IC3") (pin "15") (pinfunction "GND_15") (pintype "passive"))
      (node (ref "J2") (pin "22") (pinfunction "GND_22") (pintype "passive"))
      (node (ref "J2") (pin "25") (pinfunction "GND_25") (pintype "passive"))
      (node (ref "J3") (pin "13") (pinfunction "SHILED_13") (pintype "passive"))
      (node (ref "J3") (pin "14") (pinfunction "SHILED_14") (pintype "passive"))
      (node (ref "J3") (pin "8") (pinfunction "CHS_GND_8") (pintype "passive"))
      (node (ref "J4") (pin "10") (pinfunction "MH1_10") (pintype "passive"))
      (node (ref "J4") (pin "11") (pinfunction "MH2_11") (pintype "passive"))
      (node (ref "J4") (pin "5") (pinfunction "5_5") (pintype "passive"))
      (node (ref "JP2") (pin "2") (pinfunction "2_2") (pintype "passive"))
      (node (ref "LED1") (pin "2") (pinfunction "K_2") (pintype "passive"))
      (node (ref "R13") (pin "2") (pinfunction "2_2") (pintype "passive"))
      (node (ref "R21") (pin "1") (pinfunction "1_1") (pintype "passive"))
      (node (ref "R32") (pin "2") (pinfunction "2_2") (pintype "passive"))
      (node (ref "R34") (pin "2") (pinfunction "2_2") (pintype "passive"))
      (node (ref "R48") (pin "2") (pinfunction "2_2") (pintype "passive"))
      (node (ref "U2") (pin "2") (pinfunction "GND_2") (pintype "passive"))
      (node (ref "U3") (pin "12") (pinfunction "GND_12") (pintype "passive"))
      (node (ref "U3") (pin "34") (pinfunction "GND_34") (pintype "passive"))
      (node (ref "U4") (pin "5") (pinfunction "GND_5") (pintype "passive"))
      (node (ref "U5") (pin "15") (pinfunction "AGND_15") (pintype "passive"))
      (node (ref "U5") (pin "19") (pinfunction "AGND_19") (pintype "passive"))
      (node (ref "U5") (pin "35") (pinfunction "IOGND_35") (pintype "passive"))
      (node (ref "U5") (pin "36") (pinfunction "DGND_36") (pintype "passive"))
      (node (ref "U5") (pin "47") (pinfunction "IOGND_47") (pintype "passive"))
      (node (ref "U6") (pin "8") (pinfunction "RS_8") (pintype "passive"))
      (node (ref "USB1") (pin "5") (pinfunction "GND_5") (pintype "passive"))
      (node (ref "V1") (pin "1") (pinfunction "GND_1") (pintype "passive"))
      (node (ref "VD3") (pin "1") (pinfunction "A_1") (pintype "passive"))
      (node (ref "Y1") (pin "3") (pinfunction "g_3") (pintype "passive"))
    )
    (net (code "85") (name "Net-(CON1-Pad1)") (class "Default")
      (node (ref "CON1") (pin "1") (pintype "power_in"))
      (node (ref "F1") (pin "1") (pinfunction "1_1") (pintype "passive"))
      (node (ref "JP2") (pin "1") (pinfunction "1_1") (pintype "passive"))
    )
    (net (code "86") (name "Net-(F1-Pad2)") (class "Default")
      (node (ref "F1") (pin "2") (pinfunction "2_2") (pintype "passive"))
      (node (ref "S1") (pin "3") (pinfunction "3_3") (pintype "passive"))
    )
    (net (code "87") (name "Net-(F2-Pad1)") (class "Default")
      (node (ref "F2") (pin "1") (pinfunction "1_1") (pintype "passive"))
      (node (ref "S1") (pin "4") (pinfunction "4_4") (pintype "passive"))
    )
    (net (code "88") (name "Net-(IC3-C1+)") (class "Default")
      (node (ref "C36") (pin "1") (pinfunction "1_1") (pintype "passive"))
      (node (ref "IC3") (pin "1") (pinfunction "C1+_1") (pintype "passive"))
    )
    (net (code "89") (name "Net-(IC3-C1-)") (class "Default")
      (node (ref "C36") (pin "2") (pinfunction "2_2") (pintype "passive"))
      (node (ref "IC3") (pin "3") (pinfunction "C1-_3") (pintype "passive"))
    )
    (net (code "90") (name "Net-(IC3-C2+)") (class "Default")
      (node (ref "C45") (pin "1") (pinfunction "1_1") (pintype "passive"))
      (node (ref "IC3") (pin "4") (pinfunction "C2+_4") (pintype "passive"))
    )
    (net (code "91") (name "Net-(IC3-C2-)") (class "Default")
      (node (ref "C45") (pin "2") (pinfunction "2_2") (pintype "passive"))
      (node (ref "IC3") (pin "5") (pinfunction "C2-_5") (pintype "passive"))
    )
    (net (code "92") (name "Net-(IC3-R1IN)") (class "Default")
      (node (ref "IC3") (pin "13") (pinfunction "R1IN_13") (pintype "passive"))
      (node (ref "J4") (pin "3") (pinfunction "3_3") (pintype "passive"))
    )
    (net (code "93") (name "Net-(IC3-T1OUT)") (class "Default")
      (node (ref "IC3") (pin "14") (pinfunction "T1OUT_14") (pintype "passive"))
      (node (ref "J4") (pin "2") (pinfunction "2_2") (pintype "passive"))
    )
    (net (code "94") (name "Net-(IC3-VDD)") (class "Default")
      (node (ref "C42") (pin "2") (pinfunction "2_2") (pintype "passive"))
      (node (ref "IC3") (pin "2") (pinfunction "VDD_2") (pintype "passive"))
    )
    (net (code "95") (name "Net-(IC3-VEE)") (class "Default")
      (node (ref "C52") (pin "2") (pinfunction "2_2") (pintype "passive"))
      (node (ref "IC3") (pin "6") (pinfunction "VEE_6") (pintype "passive"))
    )
    (net (code "96") (name "Net-(J3-LED(G)_A)") (class "Default")
      (node (ref "J3") (pin "9") (pinfunction "LED(G)_A_9") (pintype "passive"))
      (node (ref "R35") (pin "1") (pinfunction "1_1") (pintype "passive"))
    )
    (net (code "97") (name "Net-(J3-LED(Y)_A)") (class "Default")
      (node (ref "J3") (pin "12") (pinfunction "LED(Y)_A_12") (pintype "passive"))
      (node (ref "R30") (pin "1") (pinfunction "1_1") (pintype "passive"))
    )
    (net (code "98") (name "Net-(J3-RD+)") (class "Default")
      (node (ref "J3") (pin "3") (pinfunction "RD+_3") (pintype "passive"))
      (node (ref "R26") (pin "2") (pinfunction "2_2") (pintype "passive"))
      (node (ref "U5") (pin "14") (pinfunction "RD+_14") (pintype "passive"))
    )
    (net (code "99") (name "Net-(J3-RD-)") (class "Default")
      (node (ref "J3") (pin "6") (pinfunction "RD-_6") (pintype "passive"))
      (node (ref "R27") (pin "2") (pinfunction "2_2") (pintype "passive"))
      (node (ref "U5") (pin "13") (pinfunction "RD-_13") (pintype "passive"))
    )
    (net (code "100") (name "Net-(J3-TD+)") (class "Default")
      (node (ref "J3") (pin "1") (pinfunction "TD+_1") (pintype "passive"))
      (node (ref "R24") (pin "2") (pinfunction "2_2") (pintype "passive"))
      (node (ref "U5") (pin "17") (pinfunction "TD+_17") (pintype "passive"))
    )
    (net (code "101") (name "Net-(J3-TD-)") (class "Default")
      (node (ref "J3") (pin "2") (pinfunction "TD-_2") (pintype "passive"))
      (node (ref "R25") (pin "2") (pinfunction "2_2") (pintype "passive"))
      (node (ref "U5") (pin "16") (pinfunction "TD-_16") (pintype "passive"))
    )
    (net (code "102") (name "Net-(LED1-A)") (class "Default")
      (node (ref "LED1") (pin "1") (pinfunction "A_1") (pintype "passive"))
      (node (ref "R16") (pin "1") (pinfunction "1_1") (pintype "passive"))
    )
    (net (code "103") (name "Net-(R39-Pad2)") (class "Default")
      (node (ref "R39") (pin "2") (pinfunction "2_2") (pintype "passive"))
      (node (ref "R42") (pin "2") (pinfunction "2_2") (pintype "passive"))
    )
    (net (code "104") (name "Net-(R40-Pad1)") (class "Default")
      (node (ref "R40") (pin "1") (pinfunction "1_1") (pintype "passive"))
      (node (ref "U5") (pin "21") (pinfunction "RESERVED_21") (pintype "passive"))
    )
    (net (code "105") (name "Net-(R41-Pad1)") (class "Default")
      (node (ref "R41") (pin "1") (pinfunction "1_1") (pintype "passive"))
      (node (ref "U5") (pin "20") (pinfunction "RESERVED_20") (pintype "passive"))
    )
    (net (code "106") (name "Net-(U2-BST)") (class "Default")
      (node (ref "C18") (pin "2") (pinfunction "2_2") (pintype "passive"))
      (node (ref "U2") (pin "1") (pinfunction "BST_1") (pintype "passive"))
    )
    (net (code "107") (name "Net-(U2-EN)") (class "Default")
      (node (ref "R14") (pin "1") (pinfunction "1_1") (pintype "passive"))
      (node (ref "U2") (pin "4") (pinfunction "EN_4") (pintype "passive"))
    )
    (net (code "108") (name "Net-(U2-FB)") (class "Default")
      (node (ref "R13") (pin "1") (pinfunction "1_1") (pintype "passive"))
      (node (ref "R15") (pin "2") (pinfunction "2_2") (pintype "passive"))
      (node (ref "U2") (pin "3") (pinfunction "FB_3") (pintype "passive"))
    )
    (net (code "109") (name "Net-(U2-IN)") (class "Default")
      (node (ref "C20") (pin "2") (pinfunction "2_2") (pintype "passive"))
      (node (ref "C21") (pin "2") (pinfunction "2_2") (pintype "passive"))
      (node (ref "R14") (pin "2") (pinfunction "2_2") (pintype "passive"))
      (node (ref "U2") (pin "5") (pinfunction "IN_5") (pintype "passive"))
      (node (ref "VD4") (pin "2") (pinfunction "K_2") (pintype "passive"))
    )
    (net (code "110") (name "Net-(U2-SW)") (class "Default")
      (node (ref "C18") (pin "1") (pinfunction "1_1") (pintype "passive"))
      (node (ref "L1") (pin "1") (pinfunction "1_1") (pintype "passive"))
      (node (ref "U2") (pin "6") (pinfunction "SW_6") (pintype "passive"))
      (node (ref "VD3") (pin "2") (pinfunction "K_2") (pintype "passive"))
    )
    (net (code "111") (name "Net-(U5-LED_SPEED{slash}AN1)") (class "Default")
      (node (ref "R45") (pin "1") (pinfunction "1_1") (pintype "passive"))
      (node (ref "U5") (pin "27") (pinfunction "LED_SPEED/AN1_27") (pintype "passive"))
    )
    (net (code "112") (name "Net-(U5-PFBIN1)") (class "Default")
      (node (ref "C48") (pin "1") (pinfunction "1_1") (pintype "passive"))
      (node (ref "C49") (pin "1") (pinfunction "1_1") (pintype "passive"))
      (node (ref "C50") (pin "1") (pinfunction "1_1") (pintype "passive"))
      (node (ref "C51") (pin "1") (pinfunction "1_1") (pintype "passive"))
      (node (ref "U5") (pin "18") (pinfunction "PFBIN1_18") (pintype "passive"))
      (node (ref "U5") (pin "23") (pinfunction "PFBOUT_23") (pintype "passive"))
      (node (ref "U5") (pin "37") (pinfunction "PFBIN2_37") (pintype "passive"))
    )
    (net (code "113") (name "Net-(U5-PWR_DOWN{slash}INT)") (class "Default")
      (node (ref "R47") (pin "1") (pinfunction "1_1") (pintype "passive"))
      (node (ref "U5") (pin "7") (pinfunction "PWR_DOWN/INT_7") (pintype "passive"))
    )
    (net (code "114") (name "Net-(U5-RBIAS)") (class "Default")
      (node (ref "R48") (pin "1") (pinfunction "1_1") (pintype "passive"))
      (node (ref "U5") (pin "24") (pinfunction "RBIAS_24") (pintype "passive"))
    )
    (net (code "115") (name "Net-(U5-RXD_0{slash}PHYAD1)") (class "Default")
      (node (ref "R36") (pin "1") (pinfunction "1_1") (pintype "passive"))
      (node (ref "U5") (pin "43") (pinfunction "RXD_0/PHYAD1_43") (pintype "passive"))
    )
    (net (code "116") (name "Net-(U5-RXD_1{slash}PHYAD2)") (class "Default")
      (node (ref "R38") (pin "1") (pinfunction "1_1") (pintype "passive"))
      (node (ref "U5") (pin "44") (pinfunction "RXD_1/PHYAD2_44") (pintype "passive"))
    )
    (net (code "117") (name "Net-(U5-TXD_0)") (class "Default")
      (node (ref "R29") (pin "1") (pinfunction "1_1") (pintype "passive"))
      (node (ref "U5") (pin "3") (pinfunction "TXD_0_3") (pintype "passive"))
    )
    (net (code "118") (name "Net-(U5-TXD_1)") (class "Default")
      (node (ref "R31") (pin "1") (pinfunction "1_1") (pintype "passive"))
      (node (ref "U5") (pin "4") (pinfunction "TXD_1_4") (pintype "passive"))
    )
    (net (code "119") (name "Net-(U5-TXD_2)") (class "Default")
      (node (ref "R32") (pin "1") (pinfunction "1_1") (pintype "passive"))
      (node (ref "U5") (pin "5") (pinfunction "TXD_2_5") (pintype "passive"))
    )
    (net (code "120") (name "Net-(U5-TXD_3{slash}SNI_MODE)") (class "Default")
      (node (ref "R34") (pin "1") (pinfunction "1_1") (pintype "passive"))
      (node (ref "U5") (pin "6") (pinfunction "TXD_3/SNI_MODE_6") (pintype "passive"))
    )
    (net (code "121") (name "Net-(U5-TX_EN)") (class "Default")
      (node (ref "R28") (pin "1") (pinfunction "1_1") (pintype "passive"))
      (node (ref "U5") (pin "2") (pinfunction "TX_EN_2") (pintype "passive"))
    )
    (net (code "122") (name "Net-(U6-GND)") (class "Default")
      (node (ref "C35") (pin "1") (pinfunction "1_1") (pintype "passive"))
      (node (ref "U6") (pin "2") (pinfunction "GND_2") (pintype "passive"))
    )
    (net (code "123") (name "Net-(USB1-+5V)") (class "Default")
      (node (ref "F2") (pin "2") (pinfunction "2_2") (pintype "passive"))
      (node (ref "USB1") (pin "1") (pinfunction "+5V_1") (pintype "passive"))
    )
    (net (code "124") (name "Net-(VD4-A)") (class "Default")
      (node (ref "S1") (pin "2") (pinfunction "2_2") (pintype "passive"))
      (node (ref "VD4") (pin "1") (pinfunction "A_1") (pintype "passive"))
    )
    (net (code "125") (name "Net-(Y1-out)") (class "Default")
      (node (ref "C43") (pin "1") (pinfunction "1_1") (pintype "passive"))
      (node (ref "C44") (pin "1") (pinfunction "1_1") (pintype "passive"))
      (node (ref "L3") (pin "1") (pinfunction "1_1") (pintype "passive"))
      (node (ref "Y1") (pin "4") (pinfunction "out_4") (pintype "passive"))
    )
    (net (code "126") (name "unconnected-(IC3-R2IN-Pad8)") (class "Default")
      (node (ref "IC3") (pin "8") (pinfunction "R2IN_8") (pintype "passive+no_connect"))
    )
    (net (code "127") (name "unconnected-(IC3-R2OUT-Pad9)") (class "Default")
      (node (ref "IC3") (pin "9") (pinfunction "R2OUT_9") (pintype "passive+no_connect"))
    )
    (net (code "128") (name "unconnected-(IC3-T2IN-Pad10)") (class "Default")
      (node (ref "IC3") (pin "10") (pinfunction "T2IN_10") (pintype "passive+no_connect"))
    )
    (net (code "129") (name "unconnected-(IC3-T2OUT-Pad7)") (class "Default")
      (node (ref "IC3") (pin "7") (pinfunction "T2OUT_7") (pintype "passive+no_connect"))
    )
    (net (code "130") (name "unconnected-(J2-NC-Pad28)") (class "Default")
      (node (ref "J2") (pin "28") (pinfunction "NC_28") (pintype "passive+no_connect"))
    )
    (net (code "131") (name "unconnected-(J3-NC-Pad7)") (class "Default")
      (node (ref "J3") (pin "7") (pinfunction "NC_7") (pintype "passive+no_connect"))
    )
    (net (code "132") (name "unconnected-(J4-Pad1)") (class "Default")
      (node (ref "J4") (pin "1") (pinfunction "1_1") (pintype "passive+no_connect"))
    )
    (net (code "133") (name "unconnected-(J4-Pad4)") (class "Default")
      (node (ref "J4") (pin "4") (pinfunction "4_4") (pintype "passive+no_connect"))
    )
    (net (code "134") (name "unconnected-(J4-Pad6)") (class "Default")
      (node (ref "J4") (pin "6") (pinfunction "6_6") (pintype "passive+no_connect"))
    )
    (net (code "135") (name "unconnected-(J4-Pad7)") (class "Default")
      (node (ref "J4") (pin "7") (pinfunction "7_7") (pintype "passive+no_connect"))
    )
    (net (code "136") (name "unconnected-(J4-Pad8)") (class "Default")
      (node (ref "J4") (pin "8") (pinfunction "8_8") (pintype "passive+no_connect"))
    )
    (net (code "137") (name "unconnected-(J4-Pad9)") (class "Default")
      (node (ref "J4") (pin "9") (pinfunction "9_9") (pintype "passive+no_connect"))
    )
    (net (code "138") (name "unconnected-(S1-Pad1)") (class "Default")
      (node (ref "S1") (pin "1") (pinfunction "1_1") (pintype "passive"))
    )
    (net (code "139") (name "unconnected-(S1-Pad6)") (class "Default")
      (node (ref "S1") (pin "6") (pinfunction "6_6") (pintype "passive"))
    )
    (net (code "140") (name "unconnected-(U5-25MHz_OUT-Pad25)") (class "Default")
      (node (ref "U5") (pin "25") (pinfunction "25MHz_OUT_25") (pintype "passive+no_connect"))
    )
    (net (code "141") (name "unconnected-(U5-COL{slash}PHYAD0-Pad42)") (class "Default")
      (node (ref "U5") (pin "42") (pinfunction "COL/PHYAD0_42") (pintype "passive+no_connect"))
    )
    (net (code "142") (name "unconnected-(U5-CRS{slash}CRS_DV{slash}LED_CFG-Pad40)") (class "Default")
      (node (ref "U5") (pin "40") (pinfunction "CRS/CRS_DV/LED_CFG_40") (pintype "passive+no_connect"))
    )
    (net (code "143") (name "unconnected-(U5-RXD_2{slash}PHYAD3-Pad45)") (class "Default")
      (node (ref "U5") (pin "45") (pinfunction "RXD_2/PHYAD3_45") (pintype "passive+no_connect"))
    )
    (net (code "144") (name "unconnected-(U5-RXD_3{slash}PHYAD4-Pad46)") (class "Default")
      (node (ref "U5") (pin "46") (pinfunction "RXD_3/PHYAD4_46") (pintype "passive+no_connect"))
    )
    (net (code "145") (name "unconnected-(U5-RX_CLK-Pad38)") (class "Default")
      (node (ref "U5") (pin "38") (pinfunction "RX_CLK_38") (pintype "passive+no_connect"))
    )
    (net (code "146") (name "unconnected-(U5-RX_ER{slash}MDIX_EN-Pad41)") (class "Default")
      (node (ref "U5") (pin "41") (pinfunction "RX_ER/MDIX_EN_41") (pintype "passive+no_connect"))
    )
    (net (code "147") (name "unconnected-(U5-TCK-Pad8)") (class "Default")
      (node (ref "U5") (pin "8") (pinfunction "TCK_8") (pintype "passive"))
    )
    (net (code "148") (name "unconnected-(U5-TDI-Pad12)") (class "Default")
      (node (ref "U5") (pin "12") (pinfunction "TDI_12") (pintype "passive"))
    )
    (net (code "149") (name "unconnected-(U5-TDO-Pad9)") (class "Default")
      (node (ref "U5") (pin "9") (pinfunction "TDO_9") (pintype "passive"))
    )
    (net (code "150") (name "unconnected-(U5-TMS-Pad10)") (class "Default")
      (node (ref "U5") (pin "10") (pinfunction "TMS_10") (pintype "passive"))
    )
    (net (code "151") (name "unconnected-(U5-TRST#-Pad11)") (class "Default")
      (node (ref "U5") (pin "11") (pinfunction "TRST#_11") (pintype "passive"))
    )
    (net (code "152") (name "unconnected-(U5-TX_CLK-Pad1)") (class "Default")
      (node (ref "U5") (pin "1") (pinfunction "TX_CLK_1") (pintype "passive+no_connect"))
    )
    (net (code "153") (name "unconnected-(U5-X2-Pad33)") (class "Default")
      (node (ref "U5") (pin "33") (pinfunction "X2_33") (pintype "passive+no_connect"))
    )
    (net (code "154") (name "unconnected-(U6-Vref-Pad5)") (class "Default")
      (node (ref "U6") (pin "5") (pinfunction "Vref_5") (pintype "passive"))
    )
    (net (code "155") (name "unconnected-(USB1-ID-Pad4)") (class "Default")
      (node (ref "USB1") (pin "4") (pinfunction "ID_4") (pintype "passive"))
    )
    (net (code "156") (name "unconnected-(Y1-g-Pad2)") (class "Default")
      (node (ref "Y1") (pin "2") (pinfunction "g_2") (pintype "passive"))
    )
  )
)
